# LED_HEADERS.net
KiCad netlist of a schematic drawn in Altium Designer
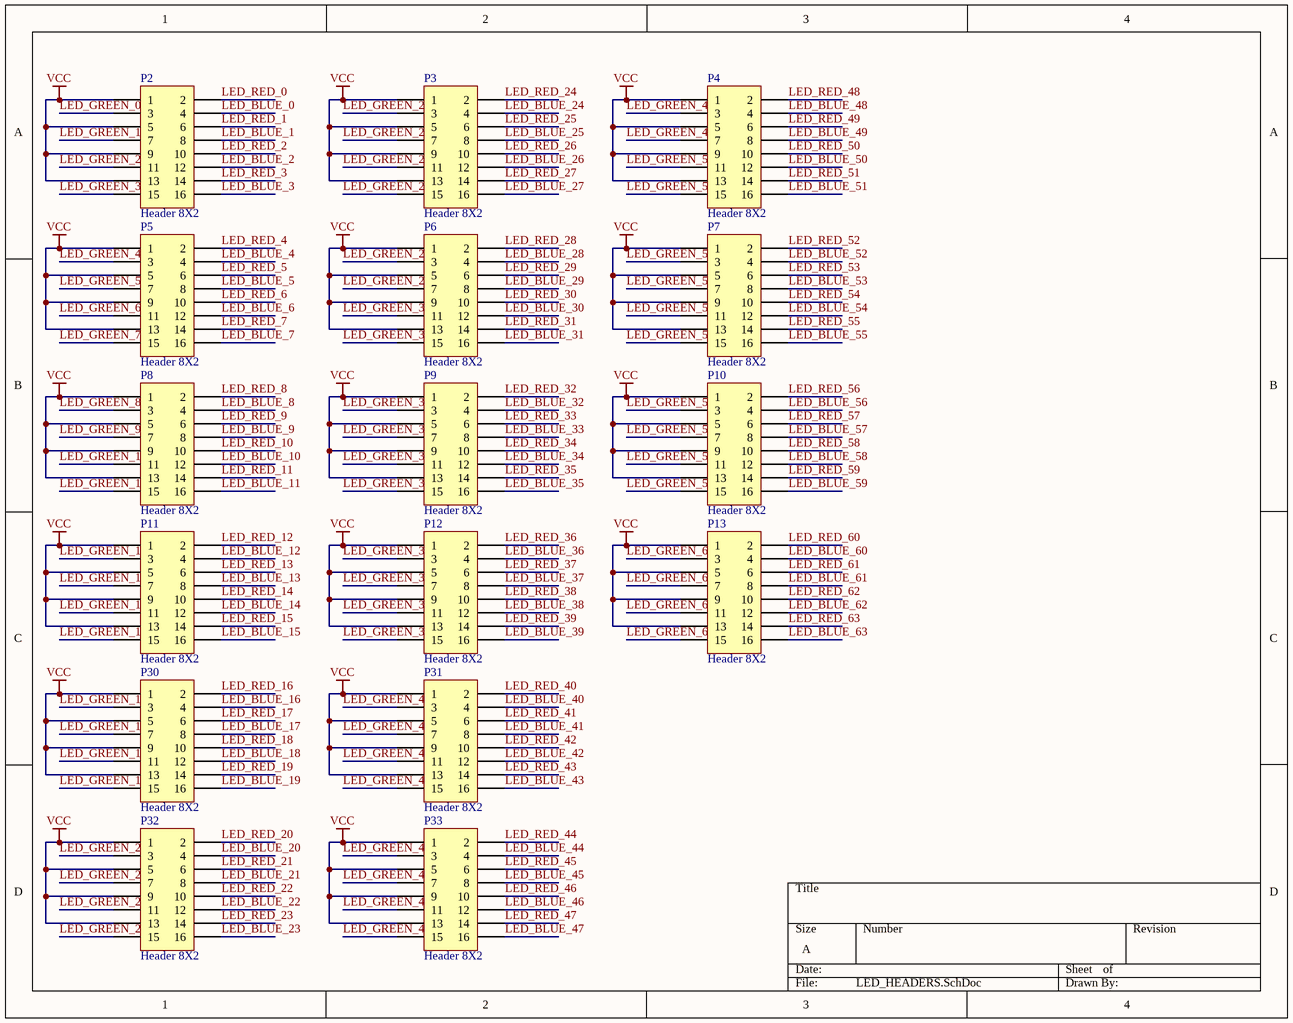
[diagram p0: LED_HEADERS.SchDoc]

(export (version "E")
  (design (tool "Eeschema 10.0.6"))
  (components
    (comp (ref "P2")
      (value "Header 8X2")
      (footprint "HDR2X8")
      (description "Header, 8-Pin, Dual row")
      (fields (field (name "PUBLISHER") "Altium Limited"))
      (libsource (lib "Miscellaneous Connectors") (part "Header 8X2"))
    )
    (comp (ref "P3")
      (value "Header 8X2")
      (footprint "HDR2X8")
      (description "Header, 8-Pin, Dual row")
      (fields (field (name "PUBLISHER") "Altium Limited"))
      (libsource (lib "Miscellaneous Connectors") (part "Header 8X2"))
    )
    (comp (ref "P4")
      (value "Header 8X2")
      (footprint "HDR2X8")
      (description "Header, 8-Pin, Dual row")
      (fields (field (name "PUBLISHER") "Altium Limited"))
      (libsource (lib "Miscellaneous Connectors") (part "Header 8X2"))
    )
    (comp (ref "P5")
      (value "Header 8X2")
      (footprint "HDR2X8")
      (description "Header, 8-Pin, Dual row")
      (fields (field (name "PUBLISHER") "Altium Limited"))
      (libsource (lib "Miscellaneous Connectors") (part "Header 8X2"))
    )
    (comp (ref "P6")
      (value "Header 8X2")
      (footprint "HDR2X8")
      (description "Header, 8-Pin, Dual row")
      (fields (field (name "PUBLISHER") "Altium Limited"))
      (libsource (lib "Miscellaneous Connectors") (part "Header 8X2"))
    )
    (comp (ref "P7")
      (value "Header 8X2")
      (footprint "HDR2X8")
      (description "Header, 8-Pin, Dual row")
      (fields (field (name "PUBLISHER") "Altium Limited"))
      (libsource (lib "Miscellaneous Connectors") (part "Header 8X2"))
    )
    (comp (ref "P8")
      (value "Header 8X2")
      (footprint "HDR2X8")
      (description "Header, 8-Pin, Dual row")
      (fields (field (name "PUBLISHER") "Altium Limited"))
      (libsource (lib "Miscellaneous Connectors") (part "Header 8X2"))
    )
    (comp (ref "P9")
      (value "Header 8X2")
      (footprint "HDR2X8")
      (description "Header, 8-Pin, Dual row")
      (fields (field (name "PUBLISHER") "Altium Limited"))
      (libsource (lib "Miscellaneous Connectors") (part "Header 8X2"))
    )
    (comp (ref "P10")
      (value "Header 8X2")
      (footprint "HDR2X8")
      (description "Header, 8-Pin, Dual row")
      (fields (field (name "PUBLISHER") "Altium Limited"))
      (libsource (lib "Miscellaneous Connectors") (part "Header 8X2"))
    )
    (comp (ref "P11")
      (value "Header 8X2")
      (footprint "HDR2X8")
      (description "Header, 8-Pin, Dual row")
      (fields (field (name "PUBLISHER") "Altium Limited"))
      (libsource (lib "Miscellaneous Connectors") (part "Header 8X2"))
    )
    (comp (ref "P12")
      (value "Header 8X2")
      (footprint "HDR2X8")
      (description "Header, 8-Pin, Dual row")
      (fields (field (name "PUBLISHER") "Altium Limited"))
      (libsource (lib "Miscellaneous Connectors") (part "Header 8X2"))
    )
    (comp (ref "P13")
      (value "Header 8X2")
      (footprint "HDR2X8")
      (description "Header, 8-Pin, Dual row")
      (fields (field (name "PUBLISHER") "Altium Limited"))
      (libsource (lib "Miscellaneous Connectors") (part "Header 8X2"))
    )
    (comp (ref "P30")
      (value "Header 8X2")
      (footprint "HDR2X8")
      (description "Header, 8-Pin, Dual row")
      (fields (field (name "PUBLISHER") "Altium Limited"))
      (libsource (lib "Miscellaneous Connectors") (part "Header 8X2"))
    )
    (comp (ref "P31")
      (value "Header 8X2")
      (footprint "HDR2X8")
      (description "Header, 8-Pin, Dual row")
      (fields (field (name "PUBLISHER") "Altium Limited"))
      (libsource (lib "Miscellaneous Connectors") (part "Header 8X2"))
    )
    (comp (ref "P32")
      (value "Header 8X2")
      (footprint "HDR2X8")
      (description "Header, 8-Pin, Dual row")
      (fields (field (name "PUBLISHER") "Altium Limited"))
      (libsource (lib "Miscellaneous Connectors") (part "Header 8X2"))
    )
    (comp (ref "P33")
      (value "Header 8X2")
      (footprint "HDR2X8")
      (description "Header, 8-Pin, Dual row")
      (fields (field (name "PUBLISHER") "Altium Limited"))
      (libsource (lib "Miscellaneous Connectors") (part "Header 8X2"))
    )
  )
  (nets
    (net (code "1") (name "/LED_BLUE_0") (class "Default")
      (node (ref "P2") (pin "4") (pinfunction "4_4") (pintype "passive"))
    )
    (net (code "2") (name "/LED_BLUE_1") (class "Default")
      (node (ref "P2") (pin "8") (pinfunction "8_8") (pintype "passive"))
    )
    (net (code "3") (name "/LED_BLUE_2") (class "Default")
      (node (ref "P2") (pin "12") (pinfunction "12_12") (pintype "passive"))
    )
    (net (code "4") (name "/LED_BLUE_3") (class "Default")
      (node (ref "P2") (pin "16") (pinfunction "16_16") (pintype "passive"))
    )
    (net (code "5") (name "/LED_BLUE_4") (class "Default")
      (node (ref "P5") (pin "4") (pinfunction "4_4") (pintype "passive"))
    )
    (net (code "6") (name "/LED_BLUE_5") (class "Default")
      (node (ref "P5") (pin "8") (pinfunction "8_8") (pintype "passive"))
    )
    (net (code "7") (name "/LED_BLUE_6") (class "Default")
      (node (ref "P5") (pin "12") (pinfunction "12_12") (pintype "passive"))
    )
    (net (code "8") (name "/LED_BLUE_7") (class "Default")
      (node (ref "P5") (pin "16") (pinfunction "16_16") (pintype "passive"))
    )
    (net (code "9") (name "/LED_BLUE_8") (class "Default")
      (node (ref "P8") (pin "4") (pinfunction "4_4") (pintype "passive"))
    )
    (net (code "10") (name "/LED_BLUE_9") (class "Default")
      (node (ref "P8") (pin "8") (pinfunction "8_8") (pintype "passive"))
    )
    (net (code "11") (name "/LED_BLUE_10") (class "Default")
      (node (ref "P8") (pin "12") (pinfunction "12_12") (pintype "passive"))
    )
    (net (code "12") (name "/LED_BLUE_11") (class "Default")
      (node (ref "P8") (pin "16") (pinfunction "16_16") (pintype "passive"))
    )
    (net (code "13") (name "/LED_BLUE_12") (class "Default")
      (node (ref "P11") (pin "4") (pinfunction "4_4") (pintype "passive"))
    )
    (net (code "14") (name "/LED_BLUE_13") (class "Default")
      (node (ref "P11") (pin "8") (pinfunction "8_8") (pintype "passive"))
    )
    (net (code "15") (name "/LED_BLUE_14") (class "Default")
      (node (ref "P11") (pin "12") (pinfunction "12_12") (pintype "passive"))
    )
    (net (code "16") (name "/LED_BLUE_15") (class "Default")
      (node (ref "P11") (pin "16") (pinfunction "16_16") (pintype "passive"))
    )
    (net (code "17") (name "/LED_BLUE_16") (class "Default")
      (node (ref "P30") (pin "4") (pinfunction "4_4") (pintype "passive"))
    )
    (net (code "18") (name "/LED_BLUE_17") (class "Default")
      (node (ref "P30") (pin "8") (pinfunction "8_8") (pintype "passive"))
    )
    (net (code "19") (name "/LED_BLUE_18") (class "Default")
      (node (ref "P30") (pin "12") (pinfunction "12_12") (pintype "passive"))
    )
    (net (code "20") (name "/LED_BLUE_19") (class "Default")
      (node (ref "P30") (pin "16") (pinfunction "16_16") (pintype "passive"))
    )
    (net (code "21") (name "/LED_BLUE_20") (class "Default")
      (node (ref "P32") (pin "4") (pinfunction "4_4") (pintype "passive"))
    )
    (net (code "22") (name "/LED_BLUE_21") (class "Default")
      (node (ref "P32") (pin "8") (pinfunction "8_8") (pintype "passive"))
    )
    (net (code "23") (name "/LED_BLUE_22") (class "Default")
      (node (ref "P32") (pin "12") (pinfunction "12_12") (pintype "passive"))
    )
    (net (code "24") (name "/LED_BLUE_23") (class "Default")
      (node (ref "P32") (pin "16") (pinfunction "16_16") (pintype "passive"))
    )
    (net (code "25") (name "/LED_BLUE_24") (class "Default")
      (node (ref "P3") (pin "4") (pinfunction "4_4") (pintype "passive"))
    )
    (net (code "26") (name "/LED_BLUE_25") (class "Default")
      (node (ref "P3") (pin "8") (pinfunction "8_8") (pintype "passive"))
    )
    (net (code "27") (name "/LED_BLUE_26") (class "Default")
      (node (ref "P3") (pin "12") (pinfunction "12_12") (pintype "passive"))
    )
    (net (code "28") (name "/LED_BLUE_27") (class "Default")
      (node (ref "P3") (pin "16") (pinfunction "16_16") (pintype "passive"))
    )
    (net (code "29") (name "/LED_BLUE_28") (class "Default")
      (node (ref "P6") (pin "4") (pinfunction "4_4") (pintype "passive"))
    )
    (net (code "30") (name "/LED_BLUE_29") (class "Default")
      (node (ref "P6") (pin "8") (pinfunction "8_8") (pintype "passive"))
    )
    (net (code "31") (name "/LED_BLUE_30") (class "Default")
      (node (ref "P6") (pin "12") (pinfunction "12_12") (pintype "passive"))
    )
    (net (code "32") (name "/LED_BLUE_31") (class "Default")
      (node (ref "P6") (pin "16") (pinfunction "16_16") (pintype "passive"))
    )
    (net (code "33") (name "/LED_BLUE_32") (class "Default")
      (node (ref "P9") (pin "4") (pinfunction "4_4") (pintype "passive"))
    )
    (net (code "34") (name "/LED_BLUE_33") (class "Default")
      (node (ref "P9") (pin "8") (pinfunction "8_8") (pintype "passive"))
    )
    (net (code "35") (name "/LED_BLUE_34") (class "Default")
      (node (ref "P9") (pin "12") (pinfunction "12_12") (pintype "passive"))
    )
    (net (code "36") (name "/LED_BLUE_35") (class "Default")
      (node (ref "P9") (pin "16") (pinfunction "16_16") (pintype "passive"))
    )
    (net (code "37") (name "/LED_BLUE_36") (class "Default")
      (node (ref "P12") (pin "4") (pinfunction "4_4") (pintype "passive"))
    )
    (net (code "38") (name "/LED_BLUE_37") (class "Default")
      (node (ref "P12") (pin "8") (pinfunction "8_8") (pintype "passive"))
    )
    (net (code "39") (name "/LED_BLUE_38") (class "Default")
      (node (ref "P12") (pin "12") (pinfunction "12_12") (pintype "passive"))
    )
    (net (code "40") (name "/LED_BLUE_39") (class "Default")
      (node (ref "P12") (pin "16") (pinfunction "16_16") (pintype "passive"))
    )
    (net (code "41") (name "/LED_BLUE_40") (class "Default")
      (node (ref "P31") (pin "4") (pinfunction "4_4") (pintype "passive"))
    )
    (net (code "42") (name "/LED_BLUE_41") (class "Default")
      (node (ref "P31") (pin "8") (pinfunction "8_8") (pintype "passive"))
    )
    (net (code "43") (name "/LED_BLUE_42") (class "Default")
      (node (ref "P31") (pin "12") (pinfunction "12_12") (pintype "passive"))
    )
    (net (code "44") (name "/LED_BLUE_43") (class "Default")
      (node (ref "P31") (pin "16") (pinfunction "16_16") (pintype "passive"))
    )
    (net (code "45") (name "/LED_BLUE_44") (class "Default")
      (node (ref "P33") (pin "4") (pinfunction "4_4") (pintype "passive"))
    )
    (net (code "46") (name "/LED_BLUE_45") (class "Default")
      (node (ref "P33") (pin "8") (pinfunction "8_8") (pintype "passive"))
    )
    (net (code "47") (name "/LED_BLUE_46") (class "Default")
      (node (ref "P33") (pin "12") (pinfunction "12_12") (pintype "passive"))
    )
    (net (code "48") (name "/LED_BLUE_47") (class "Default")
      (node (ref "P33") (pin "16") (pinfunction "16_16") (pintype "passive"))
    )
    (net (code "49") (name "/LED_BLUE_48") (class "Default")
      (node (ref "P4") (pin "4") (pinfunction "4_4") (pintype "passive"))
    )
    (net (code "50") (name "/LED_BLUE_49") (class "Default")
      (node (ref "P4") (pin "8") (pinfunction "8_8") (pintype "passive"))
    )
    (net (code "51") (name "/LED_BLUE_50") (class "Default")
      (node (ref "P4") (pin "12") (pinfunction "12_12") (pintype "passive"))
    )
    (net (code "52") (name "/LED_BLUE_51") (class "Default")
      (node (ref "P4") (pin "16") (pinfunction "16_16") (pintype "passive"))
    )
    (net (code "53") (name "/LED_BLUE_52") (class "Default")
      (node (ref "P7") (pin "4") (pinfunction "4_4") (pintype "passive"))
    )
    (net (code "54") (name "/LED_BLUE_53") (class "Default")
      (node (ref "P7") (pin "8") (pinfunction "8_8") (pintype "passive"))
    )
    (net (code "55") (name "/LED_BLUE_54") (class "Default")
      (node (ref "P7") (pin "12") (pinfunction "12_12") (pintype "passive"))
    )
    (net (code "56") (name "/LED_BLUE_55") (class "Default")
      (node (ref "P7") (pin "16") (pinfunction "16_16") (pintype "passive"))
    )
    (net (code "57") (name "/LED_BLUE_56") (class "Default")
      (node (ref "P10") (pin "4") (pinfunction "4_4") (pintype "passive"))
    )
    (net (code "58") (name "/LED_BLUE_57") (class "Default")
      (node (ref "P10") (pin "8") (pinfunction "8_8") (pintype "passive"))
    )
    (net (code "59") (name "/LED_BLUE_58") (class "Default")
      (node (ref "P10") (pin "12") (pinfunction "12_12") (pintype "passive"))
    )
    (net (code "60") (name "/LED_BLUE_59") (class "Default")
      (node (ref "P10") (pin "16") (pinfunction "16_16") (pintype "passive"))
    )
    (net (code "61") (name "/LED_BLUE_60") (class "Default")
      (node (ref "P13") (pin "4") (pinfunction "4_4") (pintype "passive"))
    )
    (net (code "62") (name "/LED_BLUE_61") (class "Default")
      (node (ref "P13") (pin "8") (pinfunction "8_8") (pintype "passive"))
    )
    (net (code "63") (name "/LED_BLUE_62") (class "Default")
      (node (ref "P13") (pin "12") (pinfunction "12_12") (pintype "passive"))
    )
    (net (code "64") (name "/LED_BLUE_63") (class "Default")
      (node (ref "P13") (pin "16") (pinfunction "16_16") (pintype "passive"))
    )
    (net (code "65") (name "/LED_GREEN_0") (class "Default")
      (node (ref "P2") (pin "3") (pinfunction "3_3") (pintype "passive"))
    )
    (net (code "66") (name "/LED_GREEN_1") (class "Default")
      (node (ref "P2") (pin "7") (pinfunction "7_7") (pintype "passive"))
    )
    (net (code "67") (name "/LED_GREEN_2") (class "Default")
      (node (ref "P2") (pin "11") (pinfunction "11_11") (pintype "passive"))
    )
    (net (code "68") (name "/LED_GREEN_3") (class "Default")
      (node (ref "P2") (pin "15") (pinfunction "15_15") (pintype "passive"))
    )
    (net (code "69") (name "/LED_GREEN_4") (class "Default")
      (node (ref "P5") (pin "3") (pinfunction "3_3") (pintype "passive"))
    )
    (net (code "70") (name "/LED_GREEN_5") (class "Default")
      (node (ref "P5") (pin "7") (pinfunction "7_7") (pintype "passive"))
    )
    (net (code "71") (name "/LED_GREEN_6") (class "Default")
      (node (ref "P5") (pin "11") (pinfunction "11_11") (pintype "passive"))
    )
    (net (code "72") (name "/LED_GREEN_7") (class "Default")
      (node (ref "P5") (pin "15") (pinfunction "15_15") (pintype "passive"))
    )
    (net (code "73") (name "/LED_GREEN_8") (class "Default")
      (node (ref "P8") (pin "3") (pinfunction "3_3") (pintype "passive"))
    )
    (net (code "74") (name "/LED_GREEN_9") (class "Default")
      (node (ref "P8") (pin "7") (pinfunction "7_7") (pintype "passive"))
    )
    (net (code "75") (name "/LED_GREEN_10") (class "Default")
      (node (ref "P8") (pin "11") (pinfunction "11_11") (pintype "passive"))
    )
    (net (code "76") (name "/LED_GREEN_11") (class "Default")
      (node (ref "P8") (pin "15") (pinfunction "15_15") (pintype "passive"))
    )
    (net (code "77") (name "/LED_GREEN_12") (class "Default")
      (node (ref "P11") (pin "3") (pinfunction "3_3") (pintype "passive"))
    )
    (net (code "78") (name "/LED_GREEN_13") (class "Default")
      (node (ref "P11") (pin "7") (pinfunction "7_7") (pintype "passive"))
    )
    (net (code "79") (name "/LED_GREEN_14") (class "Default")
      (node (ref "P11") (pin "11") (pinfunction "11_11") (pintype "passive"))
    )
    (net (code "80") (name "/LED_GREEN_15") (class "Default")
      (node (ref "P11") (pin "15") (pinfunction "15_15") (pintype "passive"))
    )
    (net (code "81") (name "/LED_GREEN_16") (class "Default")
      (node (ref "P30") (pin "3") (pinfunction "3_3") (pintype "passive"))
    )
    (net (code "82") (name "/LED_GREEN_17") (class "Default")
      (node (ref "P30") (pin "7") (pinfunction "7_7") (pintype "passive"))
    )
    (net (code "83") (name "/LED_GREEN_18") (class "Default")
      (node (ref "P30") (pin "11") (pinfunction "11_11") (pintype "passive"))
    )
    (net (code "84") (name "/LED_GREEN_19") (class "Default")
      (node (ref "P30") (pin "15") (pinfunction "15_15") (pintype "passive"))
    )
    (net (code "85") (name "/LED_GREEN_20") (class "Default")
      (node (ref "P32") (pin "3") (pinfunction "3_3") (pintype "passive"))
    )
    (net (code "86") (name "/LED_GREEN_21") (class "Default")
      (node (ref "P32") (pin "7") (pinfunction "7_7") (pintype "passive"))
    )
    (net (code "87") (name "/LED_GREEN_22") (class "Default")
      (node (ref "P32") (pin "11") (pinfunction "11_11") (pintype "passive"))
    )
    (net (code "88") (name "/LED_GREEN_23") (class "Default")
      (node (ref "P32") (pin "15") (pinfunction "15_15") (pintype "passive"))
    )
    (net (code "89") (name "/LED_GREEN_24") (class "Default")
      (node (ref "P3") (pin "3") (pinfunction "3_3") (pintype "passive"))
    )
    (net (code "90") (name "/LED_GREEN_25") (class "Default")
      (node (ref "P3") (pin "7") (pinfunction "7_7") (pintype "passive"))
    )
    (net (code "91") (name "/LED_GREEN_26") (class "Default")
      (node (ref "P3") (pin "11") (pinfunction "11_11") (pintype "passive"))
    )
    (net (code "92") (name "/LED_GREEN_27") (class "Default")
      (node (ref "P3") (pin "15") (pinfunction "15_15") (pintype "passive"))
    )
    (net (code "93") (name "/LED_GREEN_28") (class "Default")
      (node (ref "P6") (pin "3") (pinfunction "3_3") (pintype "passive"))
    )
    (net (code "94") (name "/LED_GREEN_29") (class "Default")
      (node (ref "P6") (pin "7") (pinfunction "7_7") (pintype "passive"))
    )
    (net (code "95") (name "/LED_GREEN_30") (class "Default")
      (node (ref "P6") (pin "11") (pinfunction "11_11") (pintype "passive"))
    )
    (net (code "96") (name "/LED_GREEN_31") (class "Default")
      (node (ref "P6") (pin "15") (pinfunction "15_15") (pintype "passive"))
    )
    (net (code "97") (name "/LED_GREEN_32") (class "Default")
      (node (ref "P9") (pin "3") (pinfunction "3_3") (pintype "passive"))
    )
    (net (code "98") (name "/LED_GREEN_33") (class "Default")
      (node (ref "P9") (pin "7") (pinfunction "7_7") (pintype "passive"))
    )
    (net (code "99") (name "/LED_GREEN_34") (class "Default")
      (node (ref "P9") (pin "11") (pinfunction "11_11") (pintype "passive"))
    )
    (net (code "100") (name "/LED_GREEN_35") (class "Default")
      (node (ref "P9") (pin "15") (pinfunction "15_15") (pintype "passive"))
    )
    (net (code "101") (name "/LED_GREEN_36") (class "Default")
      (node (ref "P12") (pin "3") (pinfunction "3_3") (pintype "passive"))
    )
    (net (code "102") (name "/LED_GREEN_37") (class "Default")
      (node (ref "P12") (pin "7") (pinfunction "7_7") (pintype "passive"))
    )
    (net (code "103") (name "/LED_GREEN_38") (class "Default")
      (node (ref "P12") (pin "11") (pinfunction "11_11") (pintype "passive"))
    )
    (net (code "104") (name "/LED_GREEN_39") (class "Default")
      (node (ref "P12") (pin "15") (pinfunction "15_15") (pintype "passive"))
    )
    (net (code "105") (name "/LED_GREEN_40") (class "Default")
      (node (ref "P31") (pin "3") (pinfunction "3_3") (pintype "passive"))
    )
    (net (code "106") (name "/LED_GREEN_41") (class "Default")
      (node (ref "P31") (pin "7") (pinfunction "7_7") (pintype "passive"))
    )
    (net (code "107") (name "/LED_GREEN_42") (class "Default")
      (node (ref "P31") (pin "11") (pinfunction "11_11") (pintype "passive"))
    )
    (net (code "108") (name "/LED_GREEN_43") (class "Default")
      (node (ref "P31") (pin "15") (pinfunction "15_15") (pintype "passive"))
    )
    (net (code "109") (name "/LED_GREEN_44") (class "Default")
      (node (ref "P33") (pin "3") (pinfunction "3_3") (pintype "passive"))
    )
    (net (code "110") (name "/LED_GREEN_45") (class "Default")
      (node (ref "P33") (pin "7") (pinfunction "7_7") (pintype "passive"))
    )
    (net (code "111") (name "/LED_GREEN_46") (class "Default")
      (node (ref "P33") (pin "11") (pinfunction "11_11") (pintype "passive"))
    )
    (net (code "112") (name "/LED_GREEN_47") (class "Default")
      (node (ref "P33") (pin "15") (pinfunction "15_15") (pintype "passive"))
    )
    (net (code "113") (name "/LED_GREEN_48") (class "Default")
      (node (ref "P4") (pin "3") (pinfunction "3_3") (pintype "passive"))
    )
    (net (code "114") (name "/LED_GREEN_49") (class "Default")
      (node (ref "P4") (pin "7") (pinfunction "7_7") (pintype "passive"))
    )
    (net (code "115") (name "/LED_GREEN_50") (class "Default")
      (node (ref "P4") (pin "11") (pinfunction "11_11") (pintype "passive"))
    )
    (net (code "116") (name "/LED_GREEN_51") (class "Default")
      (node (ref "P4") (pin "15") (pinfunction "15_15") (pintype "passive"))
    )
    (net (code "117") (name "/LED_GREEN_52") (class "Default")
      (node (ref "P7") (pin "3") (pinfunction "3_3") (pintype "passive"))
    )
    (net (code "118") (name "/LED_GREEN_53") (class "Default")
      (node (ref "P7") (pin "7") (pinfunction "7_7") (pintype "passive"))
    )
    (net (code "119") (name "/LED_GREEN_54") (class "Default")
      (node (ref "P7") (pin "11") (pinfunction "11_11") (pintype "passive"))
    )
    (net (code "120") (name "/LED_GREEN_55") (class "Default")
      (node (ref "P7") (pin "15") (pinfunction "15_15") (pintype "passive"))
    )
    (net (code "121") (name "/LED_GREEN_56") (class "Default")
      (node (ref "P10") (pin "3") (pinfunction "3_3") (pintype "passive"))
    )
    (net (code "122") (name "/LED_GREEN_57") (class "Default")
      (node (ref "P10") (pin "7") (pinfunction "7_7") (pintype "passive"))
    )
    (net (code "123") (name "/LED_GREEN_58") (class "Default")
      (node (ref "P10") (pin "11") (pinfunction "11_11") (pintype "passive"))
    )
    (net (code "124") (name "/LED_GREEN_59") (class "Default")
      (node (ref "P10") (pin "15") (pinfunction "15_15") (pintype "passive"))
    )
    (net (code "125") (name "/LED_GREEN_60") (class "Default")
      (node (ref "P13") (pin "3") (pinfunction "3_3") (pintype "passive"))
    )
    (net (code "126") (name "/LED_GREEN_61") (class "Default")
      (node (ref "P13") (pin "7") (pinfunction "7_7") (pintype "passive"))
    )
    (net (code "127") (name "/LED_GREEN_62") (class "Default")
      (node (ref "P13") (pin "11") (pinfunction "11_11") (pintype "passive"))
    )
    (net (code "128") (name "/LED_GREEN_63") (class "Default")
      (node (ref "P13") (pin "15") (pinfunction "15_15") (pintype "passive"))
    )
    (net (code "129") (name "/LED_RED_0") (class "Default")
      (node (ref "P2") (pin "2") (pinfunction "2_2") (pintype "passive"))
    )
    (net (code "130") (name "/LED_RED_1") (class "Default")
      (node (ref "P2") (pin "6") (pinfunction "6_6") (pintype "passive"))
    )
    (net (code "131") (name "/LED_RED_2") (class "Default")
      (node (ref "P2") (pin "10") (pinfunction "10_10") (pintype "passive"))
    )
    (net (code "132") (name "/LED_RED_3") (class "Default")
      (node (ref "P2") (pin "14") (pinfunction "14_14") (pintype "passive"))
    )
    (net (code "133") (name "/LED_RED_4") (class "Default")
      (node (ref "P5") (pin "2") (pinfunction "2_2") (pintype "passive"))
    )
    (net (code "134") (name "/LED_RED_5") (class "Default")
      (node (ref "P5") (pin "6") (pinfunction "6_6") (pintype "passive"))
    )
    (net (code "135") (name "/LED_RED_6") (class "Default")
      (node (ref "P5") (pin "10") (pinfunction "10_10") (pintype "passive"))
    )
    (net (code "136") (name "/LED_RED_7") (class "Default")
      (node (ref "P5") (pin "14") (pinfunction "14_14") (pintype "passive"))
    )
    (net (code "137") (name "/LED_RED_8") (class "Default")
      (node (ref "P8") (pin "2") (pinfunction "2_2") (pintype "passive"))
    )
    (net (code "138") (name "/LED_RED_9") (class "Default")
      (node (ref "P8") (pin "6") (pinfunction "6_6") (pintype "passive"))
    )
    (net (code "139") (name "/LED_RED_10") (class "Default")
      (node (ref "P8") (pin "10") (pinfunction "10_10") (pintype "passive"))
    )
    (net (code "140") (name "/LED_RED_11") (class "Default")
      (node (ref "P8") (pin "14") (pinfunction "14_14") (pintype "passive"))
    )
    (net (code "141") (name "/LED_RED_12") (class "Default")
      (node (ref "P11") (pin "2") (pinfunction "2_2") (pintype "passive"))
    )
    (net (code "142") (name "/LED_RED_13") (class "Default")
      (node (ref "P11") (pin "6") (pinfunction "6_6") (pintype "passive"))
    )
    (net (code "143") (name "/LED_RED_14") (class "Default")
      (node (ref "P11") (pin "10") (pinfunction "10_10") (pintype "passive"))
    )
    (net (code "144") (name "/LED_RED_15") (class "Default")
      (node (ref "P11") (pin "14") (pinfunction "14_14") (pintype "passive"))
    )
    (net (code "145") (name "/LED_RED_16") (class "Default")
      (node (ref "P30") (pin "2") (pinfunction "2_2") (pintype "passive"))
    )
    (net (code "146") (name "/LED_RED_17") (class "Default")
      (node (ref "P30") (pin "6") (pinfunction "6_6") (pintype "passive"))
    )
    (net (code "147") (name "/LED_RED_18") (class "Default")
      (node (ref "P30") (pin "10") (pinfunction "10_10") (pintype "passive"))
    )
    (net (code "148") (name "/LED_RED_19") (class "Default")
      (node (ref "P30") (pin "14") (pinfunction "14_14") (pintype "passive"))
    )
    (net (code "149") (name "/LED_RED_20") (class "Default")
      (node (ref "P32") (pin "2") (pinfunction "2_2") (pintype "passive"))
    )
    (net (code "150") (name "/LED_RED_21") (class "Default")
      (node (ref "P32") (pin "6") (pinfunction "6_6") (pintype "passive"))
    )
    (net (code "151") (name "/LED_RED_22") (class "Default")
      (node (ref "P32") (pin "10") (pinfunction "10_10") (pintype "passive"))
    )
    (net (code "152") (name "/LED_RED_23") (class "Default")
      (node (ref "P32") (pin "14") (pinfunction "14_14") (pintype "passive"))
    )
    (net (code "153") (name "/LED_RED_24") (class "Default")
      (node (ref "P3") (pin "2") (pinfunction "2_2") (pintype "passive"))
    )
    (net (code "154") (name "/LED_RED_25") (class "Default")
      (node (ref "P3") (pin "6") (pinfunction "6_6") (pintype "passive"))
    )
    (net (code "155") (name "/LED_RED_26") (class "Default")
      (node (ref "P3") (pin "10") (pinfunction "10_10") (pintype "passive"))
    )
    (net (code "156") (name "/LED_RED_27") (class "Default")
      (node (ref "P3") (pin "14") (pinfunction "14_14") (pintype "passive"))
    )
    (net (code "157") (name "/LED_RED_28") (class "Default")
      (node (ref "P6") (pin "2") (pinfunction "2_2") (pintype "passive"))
    )
    (net (code "158") (name "/LED_RED_29") (class "Default")
      (node (ref "P6") (pin "6") (pinfunction "6_6") (pintype "passive"))
    )
    (net (code "159") (name "/LED_RED_30") (class "Default")
      (node (ref "P6") (pin "10") (pinfunction "10_10") (pintype "passive"))
    )
    (net (code "160") (name "/LED_RED_31") (class "Default")
      (node (ref "P6") (pin "14") (pinfunction "14_14") (pintype "passive"))
    )
    (net (code "161") (name "/LED_RED_32") (class "Default")
      (node (ref "P9") (pin "2") (pinfunction "2_2") (pintype "passive"))
    )
    (net (code "162") (name "/LED_RED_33") (class "Default")
      (node (ref "P9") (pin "6") (pinfunction "6_6") (pintype "passive"))
    )
    (net (code "163") (name "/LED_RED_34") (class "Default")
      (node (ref "P9") (pin "10") (pinfunction "10_10") (pintype "passive"))
    )
    (net (code "164") (name "/LED_RED_35") (class "Default")
      (node (ref "P9") (pin "14") (pinfunction "14_14") (pintype "passive"))
    )
    (net (code "165") (name "/LED_RED_36") (class "Default")
      (node (ref "P12") (pin "2") (pinfunction "2_2") (pintype "passive"))
    )
    (net (code "166") (name "/LED_RED_37") (class "Default")
      (node (ref "P12") (pin "6") (pinfunction "6_6") (pintype "passive"))
    )
    (net (code "167") (name "/LED_RED_38") (class "Default")
      (node (ref "P12") (pin "10") (pinfunction "10_10") (pintype "passive"))
    )
    (net (code "168") (name "/LED_RED_39") (class "Default")
      (node (ref "P12") (pin "14") (pinfunction "14_14") (pintype "passive"))
    )
    (net (code "169") (name "/LED_RED_40") (class "Default")
      (node (ref "P31") (pin "2") (pinfunction "2_2") (pintype "passive"))
    )
    (net (code "170") (name "/LED_RED_41") (class "Default")
      (node (ref "P31") (pin "6") (pinfunction "6_6") (pintype "passive"))
    )
    (net (code "171") (name "/LED_RED_42") (class "Default")
      (node (ref "P31") (pin "10") (pinfunction "10_10") (pintype "passive"))
    )
    (net (code "172") (name "/LED_RED_43") (class "Default")
      (node (ref "P31") (pin "14") (pinfunction "14_14") (pintype "passive"))
    )
    (net (code "173") (name "/LED_RED_44") (class "Default")
      (node (ref "P33") (pin "2") (pinfunction "2_2") (pintype "passive"))
    )
    (net (code "174") (name "/LED_RED_45") (class "Default")
      (node (ref "P33") (pin "6") (pinfunction "6_6") (pintype "passive"))
    )
    (net (code "175") (name "/LED_RED_46") (class "Default")
      (node (ref "P33") (pin "10") (pinfunction "10_10") (pintype "passive"))
    )
    (net (code "176") (name "/LED_RED_47") (class "Default")
      (node (ref "P33") (pin "14") (pinfunction "14_14") (pintype "passive"))
    )
    (net (code "177") (name "/LED_RED_48") (class "Default")
      (node (ref "P4") (pin "2") (pinfunction "2_2") (pintype "passive"))
    )
    (net (code "178") (name "/LED_RED_49") (class "Default")
      (node (ref "P4") (pin "6") (pinfunction "6_6") (pintype "passive"))
    )
    (net (code "179") (name "/LED_RED_50") (class "Default")
      (node (ref "P4") (pin "10") (pinfunction "10_10") (pintype "passive"))
    )
    (net (code "180") (name "/LED_RED_51") (class "Default")
      (node (ref "P4") (pin "14") (pinfunction "14_14") (pintype "passive"))
    )
    (net (code "181") (name "/LED_RED_52") (class "Default")
      (node (ref "P7") (pin "2") (pinfunction "2_2") (pintype "passive"))
    )
    (net (code "182") (name "/LED_RED_53") (class "Default")
      (node (ref "P7") (pin "6") (pinfunction "6_6") (pintype "passive"))
    )
    (net (code "183") (name "/LED_RED_54") (class "Default")
      (node (ref "P7") (pin "10") (pinfunction "10_10") (pintype "passive"))
    )
    (net (code "184") (name "/LED_RED_55") (class "Default")
      (node (ref "P7") (pin "14") (pinfunction "14_14") (pintype "passive"))
    )
    (net (code "185") (name "/LED_RED_56") (class "Default")
      (node (ref "P10") (pin "2") (pinfunction "2_2") (pintype "passive"))
    )
    (net (code "186") (name "/LED_RED_57") (class "Default")
      (node (ref "P10") (pin "6") (pinfunction "6_6") (pintype "passive"))
    )
    (net (code "187") (name "/LED_RED_58") (class "Default")
      (node (ref "P10") (pin "10") (pinfunction "10_10") (pintype "passive"))
    )
    (net (code "188") (name "/LED_RED_59") (class "Default")
      (node (ref "P10") (pin "14") (pinfunction "14_14") (pintype "passive"))
    )
    (net (code "189") (name "/LED_RED_60") (class "Default")
      (node (ref "P13") (pin "2") (pinfunction "2_2") (pintype "passive"))
    )
    (net (code "190") (name "/LED_RED_61") (class "Default")
      (node (ref "P13") (pin "6") (pinfunction "6_6") (pintype "passive"))
    )
    (net (code "191") (name "/LED_RED_62") (class "Default")
      (node (ref "P13") (pin "10") (pinfunction "10_10") (pintype "passive"))
    )
    (net (code "192") (name "/LED_RED_63") (class "Default")
      (node (ref "P13") (pin "14") (pinfunction "14_14") (pintype "passive"))
    )
    (net (code "193") (name "VCC") (class "Default")
      (node (ref "P10") (pin "1") (pinfunction "1_1") (pintype "passive"))
      (node (ref "P10") (pin "13") (pinfunction "13_13") (pintype "passive"))
      (node (ref "P10") (pin "5") (pinfunction "5_5") (pintype "passive"))
      (node (ref "P10") (pin "9") (pinfunction "9_9") (pintype "passive"))
      (node (ref "P11") (pin "1") (pinfunction "1_1") (pintype "passive"))
      (node (ref "P11") (pin "13") (pinfunction "13_13") (pintype "passive"))
      (node (ref "P11") (pin "5") (pinfunction "5_5") (pintype "passive"))
      (node (ref "P11") (pin "9") (pinfunction "9_9") (pintype "passive"))
      (node (ref "P12") (pin "1") (pinfunction "1_1") (pintype "passive"))
      (node (ref "P12") (pin "13") (pinfunction "13_13") (pintype "passive"))
      (node (ref "P12") (pin "5") (pinfunction "5_5") (pintype "passive"))
      (node (ref "P12") (pin "9") (pinfunction "9_9") (pintype "passive"))
      (node (ref "P13") (pin "1") (pinfunction "1_1") (pintype "passive"))
      (node (ref "P13") (pin "13") (pinfunction "13_13") (pintype "passive"))
      (node (ref "P13") (pin "5") (pinfunction "5_5") (pintype "passive"))
      (node (ref "P13") (pin "9") (pinfunction "9_9") (pintype "passive"))
      (node (ref "P2") (pin "1") (pinfunction "1_1") (pintype "passive"))
      (node (ref "P2") (pin "13") (pinfunction "13_13") (pintype "passive"))
      (node (ref "P2") (pin "5") (pinfunction "5_5") (pintype "passive"))
      (node (ref "P2") (pin "9") (pinfunction "9_9") (pintype "passive"))
      (node (ref "P3") (pin "1") (pinfunction "1_1") (pintype "passive"))
      (node (ref "P3") (pin "13") (pinfunction "13_13") (pintype "passive"))
      (node (ref "P3") (pin "5") (pinfunction "5_5") (pintype "passive"))
      (node (ref "P3") (pin "9") (pinfunction "9_9") (pintype "passive"))
      (node (ref "P30") (pin "1") (pinfunction "1_1") (pintype "passive"))
      (node (ref "P30") (pin "13") (pinfunction "13_13") (pintype "passive"))
      (node (ref "P30") (pin "5") (pinfunction "5_5") (pintype "passive"))
      (node (ref "P30") (pin "9") (pinfunction "9_9") (pintype "passive"))
      (node (ref "P31") (pin "1") (pinfunction "1_1") (pintype "passive"))
      (node (ref "P31") (pin "13") (pinfunction "13_13") (pintype "passive"))
      (node (ref "P31") (pin "5") (pinfunction "5_5") (pintype "passive"))
      (node (ref "P31") (pin "9") (pinfunction "9_9") (pintype "passive"))
      (node (ref "P32") (pin "1") (pinfunction "1_1") (pintype "passive"))
      (node (ref "P32") (pin "13") (pinfunction "13_13") (pintype "passive"))
      (node (ref "P32") (pin "5") (pinfunction "5_5") (pintype "passive"))
      (node (ref "P32") (pin "9") (pinfunction "9_9") (pintype "passive"))
      (node (ref "P33") (pin "1") (pinfunction "1_1") (pintype "passive"))
      (node (ref "P33") (pin "13") (pinfunction "13_13") (pintype "passive"))
      (node (ref "P33") (pin "5") (pinfunction "5_5") (pintype "passive"))
      (node (ref "P33") (pin "9") (pinfunction "9_9") (pintype "passive"))
      (node (ref "P4") (pin "1") (pinfunction "1_1") (pintype "passive"))
      (node (ref "P4") (pin "13") (pinfunction "13_13") (pintype "passive"))
      (node (ref "P4") (pin "5") (pinfunction "5_5") (pintype "passive"))
      (node (ref "P4") (pin "9") (pinfunction "9_9") (pintype "passive"))
      (node (ref "P5") (pin "1") (pinfunction "1_1") (pintype "passive"))
      (node (ref "P5") (pin "13") (pinfunction "13_13") (pintype "passive"))
      (node (ref "P5") (pin "5") (pinfunction "5_5") (pintype "passive"))
      (node (ref "P5") (pin "9") (pinfunction "9_9") (pintype "passive"))
      (node (ref "P6") (pin "1") (pinfunction "1_1") (pintype "passive"))
      (node (ref "P6") (pin "13") (pinfunction "13_13") (pintype "passive"))
      (node (ref "P6") (pin "5") (pinfunction "5_5") (pintype "passive"))
      (node (ref "P6") (pin "9") (pinfunction "9_9") (pintype "passive"))
      (node (ref "P7") (pin "1") (pinfunction "1_1") (pintype "passive"))
      (node (ref "P7") (pin "13") (pinfunction "13_13") (pintype "passive"))
      (node (ref "P7") (pin "5") (pinfunction "5_5") (pintype "passive"))
      (node (ref "P7") (pin "9") (pinfunction "9_9") (pintype "passive"))
      (node (ref "P8") (pin "1") (pinfunction "1_1") (pintype "passive"))
      (node (ref "P8") (pin "13") (pinfunction "13_13") (pintype "passive"))
      (node (ref "P8") (pin "5") (pinfunction "5_5") (pintype "passive"))
      (node (ref "P8") (pin "9") (pinfunction "9_9") (pintype "passive"))
      (node (ref "P9") (pin "1") (pinfunction "1_1") (pintype "passive"))
      (node (ref "P9") (pin "13") (pinfunction "13_13") (pintype "passive"))
      (node (ref "P9") (pin "5") (pinfunction "5_5") (pintype "passive"))
      (node (ref "P9") (pin "9") (pinfunction "9_9") (pintype "passive"))
    )
  )
)
